# solderpaste_dispenser.net
KiCad netlist of a schematic drawn in EAGLE
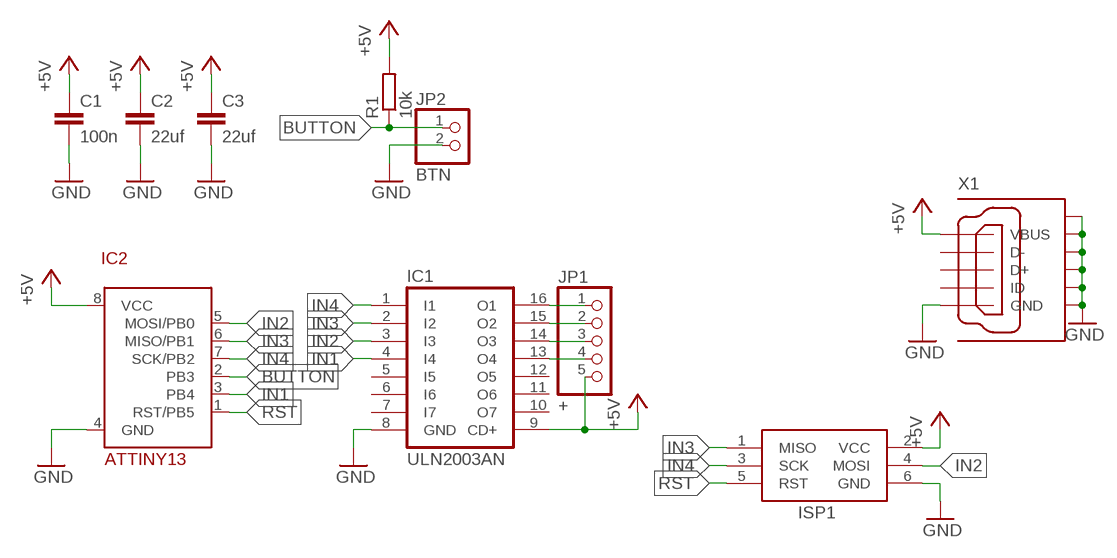
[diagram p0: schematic, sheet 1]

(export (version "E")
  (design (tool "Eeschema 10.0.6"))
  (components
    (comp (ref "C1")
      (value "100n")
      (footprint "eagle-import:C1206")
      (libsource (lib "eagle-import") (part "C-EUC1206"))
    )
    (comp (ref "C2")
      (value "22uf")
      (footprint "eagle-import:C1206")
      (libsource (lib "eagle-import") (part "C-EUC1206"))
    )
    (comp (ref "C3")
      (value "22uf")
      (footprint "eagle-import:C1206")
      (libsource (lib "eagle-import") (part "C-EUC1206"))
    )
    (comp (ref "IC1")
      (value "ULN2003AN")
      (footprint "eagle-import:DIL16")
      (libsource (lib "eagle-import") (part "ULN2003AN"))
    )
    (comp (ref "IC2")
      (value "ATTINY13")
      (footprint "eagle-import:SOIC8")
      (libsource (lib "eagle-import") (part "ATTINY13-20SU"))
    )
    (comp (ref "ISP1")
      (value "AVRISP-6")
      (footprint "eagle-import:AVRISP")
      (libsource (lib "eagle-import") (part "AVRISP-6"))
    )
    (comp (ref "JP1")
      (value "+")
      (footprint "eagle-import:1X05")
      (libsource (lib "eagle-import") (part "PINHD-1X5"))
    )
    (comp (ref "JP2")
      (value "BTN")
      (footprint "eagle-import:1X02")
      (libsource (lib "eagle-import") (part "PINHD-1X2"))
    )
    (comp (ref "R1")
      (value "10k")
      (footprint "eagle-import:M1206")
      (libsource (lib "eagle-import") (part "R-EU_M1206"))
    )
    (comp (ref "X1")
      (value "GHI-CONNECTORS_10118192-0001LF")
      (footprint "eagle-import:GHI-CONNECTORS_10118192-0001LF(MICRO-USB-B-AMPHENOL-FCI)")
      (libsource (lib "eagle-import") (part "GHI-CONNECTORS_10118192-0001LF"))
    )
  )
  (nets
    (net (code "1") (name "+5V") (class "Default")
      (node (ref "C1") (pin "1") (pinfunction "1_1") (pintype "passive"))
      (node (ref "C2") (pin "1") (pinfunction "1_1") (pintype "passive"))
      (node (ref "C3") (pin "1") (pinfunction "1_1") (pintype "passive"))
      (node (ref "IC1") (pin "9") (pinfunction "CD+_9") (pintype "passive"))
      (node (ref "IC2") (pin "8") (pinfunction "VCC_8") (pintype "power_in"))
      (node (ref "ISP1") (pin "2") (pinfunction "VCC_2") (pintype "power_in"))
      (node (ref "JP1") (pin "5") (pinfunction "5_5") (pintype "passive"))
      (node (ref "R1") (pin "2") (pinfunction "2_2") (pintype "passive"))
      (node (ref "X1") (pin "VBUS") (pinfunction "VBUS_VBUS") (pintype "input"))
    )
    (net (code "2") (name "BUTTON") (class "Default")
      (node (ref "IC2") (pin "2") (pinfunction "PB3_2") (pintype "bidirectional"))
      (node (ref "JP2") (pin "1") (pinfunction "1_1") (pintype "passive"))
      (node (ref "R1") (pin "1") (pinfunction "1_1") (pintype "passive"))
    )
    (net (code "3") (name "GND") (class "Default")
      (node (ref "C1") (pin "2") (pinfunction "2_2") (pintype "passive"))
      (node (ref "C2") (pin "2") (pinfunction "2_2") (pintype "passive"))
      (node (ref "C3") (pin "2") (pinfunction "2_2") (pintype "passive"))
      (node (ref "IC1") (pin "8") (pinfunction "GND_8") (pintype "power_in"))
      (node (ref "IC2") (pin "4") (pinfunction "GND_4") (pintype "power_in"))
      (node (ref "ISP1") (pin "6") (pinfunction "GND_6") (pintype "power_in"))
      (node (ref "JP2") (pin "2") (pinfunction "2_2") (pintype "passive"))
      (node (ref "X1") (pin "CGND1") (pinfunction "SGND1_CGND1") (pintype "bidirectional"))
      (node (ref "X1") (pin "CGND2") (pinfunction "SGND2_CGND2") (pintype "bidirectional"))
      (node (ref "X1") (pin "CGND3") (pinfunction "SGND3_CGND3") (pintype "bidirectional"))
      (node (ref "X1") (pin "CGND4") (pinfunction "SGND4_CGND4") (pintype "bidirectional"))
      (node (ref "X1") (pin "CGND5") (pinfunction "SGND5_CGND5") (pintype "bidirectional"))
      (node (ref "X1") (pin "CGND6") (pinfunction "SGND6_CGND6") (pintype "bidirectional"))
      (node (ref "X1") (pin "GND") (pinfunction "GND_GND") (pintype "input"))
    )
    (net (code "4") (name "IN1") (class "Default")
      (node (ref "IC1") (pin "4") (pinfunction "I4_4") (pintype "input"))
      (node (ref "IC2") (pin "3") (pinfunction "PB4_3") (pintype "bidirectional"))
    )
    (net (code "5") (name "IN2") (class "Default")
      (node (ref "IC1") (pin "3") (pinfunction "I3_3") (pintype "input"))
      (node (ref "IC2") (pin "5") (pinfunction "MOSI/PB0_5") (pintype "bidirectional"))
      (node (ref "ISP1") (pin "4") (pinfunction "MOSI_4") (pintype "output"))
    )
    (net (code "6") (name "IN3") (class "Default")
      (node (ref "IC1") (pin "2") (pinfunction "I2_2") (pintype "input"))
      (node (ref "IC2") (pin "6") (pinfunction "MISO/PB1_6") (pintype "bidirectional"))
      (node (ref "ISP1") (pin "1") (pinfunction "MISO_1") (pintype "input"))
    )
    (net (code "7") (name "IN4") (class "Default")
      (node (ref "IC1") (pin "1") (pinfunction "I1_1") (pintype "input"))
      (node (ref "IC2") (pin "7") (pinfunction "SCK/PB2_7") (pintype "bidirectional"))
      (node (ref "ISP1") (pin "3") (pinfunction "SCK_3") (pintype "output"))
    )
    (net (code "8") (name "Net-(IC1-O1)") (class "Default")
      (node (ref "IC1") (pin "16") (pinfunction "O1_16") (pintype "open_collector"))
      (node (ref "JP1") (pin "1") (pinfunction "1_1") (pintype "passive"))
    )
    (net (code "9") (name "Net-(IC1-O2)") (class "Default")
      (node (ref "IC1") (pin "15") (pinfunction "O2_15") (pintype "open_collector"))
      (node (ref "JP1") (pin "2") (pinfunction "2_2") (pintype "passive"))
    )
    (net (code "10") (name "Net-(IC1-O3)") (class "Default")
      (node (ref "IC1") (pin "14") (pinfunction "O3_14") (pintype "open_collector"))
      (node (ref "JP1") (pin "3") (pinfunction "3_3") (pintype "passive"))
    )
    (net (code "11") (name "Net-(IC1-O4)") (class "Default")
      (node (ref "IC1") (pin "13") (pinfunction "O4_13") (pintype "open_collector"))
      (node (ref "JP1") (pin "4") (pinfunction "4_4") (pintype "passive"))
    )
    (net (code "12") (name "RST") (class "Default")
      (node (ref "IC2") (pin "1") (pinfunction "RST/PB5_1") (pintype "bidirectional"))
      (node (ref "ISP1") (pin "5") (pinfunction "RST_5") (pintype "output"))
    )
    (net (code "13") (name "unconnected-(IC1-I5-Pad5)") (class "Default")
      (node (ref "IC1") (pin "5") (pinfunction "I5_5") (pintype "input"))
    )
    (net (code "14") (name "unconnected-(IC1-I6-Pad6)") (class "Default")
      (node (ref "IC1") (pin "6") (pinfunction "I6_6") (pintype "input"))
    )
    (net (code "15") (name "unconnected-(IC1-I7-Pad7)") (class "Default")
      (node (ref "IC1") (pin "7") (pinfunction "I7_7") (pintype "input"))
    )
    (net (code "16") (name "unconnected-(IC1-O5-Pad12)") (class "Default")
      (node (ref "IC1") (pin "12") (pinfunction "O5_12") (pintype "open_collector"))
    )
    (net (code "17") (name "unconnected-(IC1-O6-Pad11)") (class "Default")
      (node (ref "IC1") (pin "11") (pinfunction "O6_11") (pintype "open_collector"))
    )
    (net (code "18") (name "unconnected-(IC1-O7-Pad10)") (class "Default")
      (node (ref "IC1") (pin "10") (pinfunction "O7_10") (pintype "open_collector"))
    )
    (net (code "19") (name "unconnected-(X1-PadD+)") (class "Default")
      (node (ref "X1") (pin "D+") (pinfunction "D+_D+") (pintype "input"))
    )
    (net (code "20") (name "unconnected-(X1-PadD-)") (class "Default")
      (node (ref "X1") (pin "D-") (pinfunction "D-_D-") (pintype "input"))
    )
    (net (code "21") (name "unconnected-(X1-PadID)") (class "Default")
      (node (ref "X1") (pin "ID") (pinfunction "ID_ID") (pintype "input"))
    )
  )
)
